# Car02.net
KiCad netlist of a schematic drawn in EAGLE
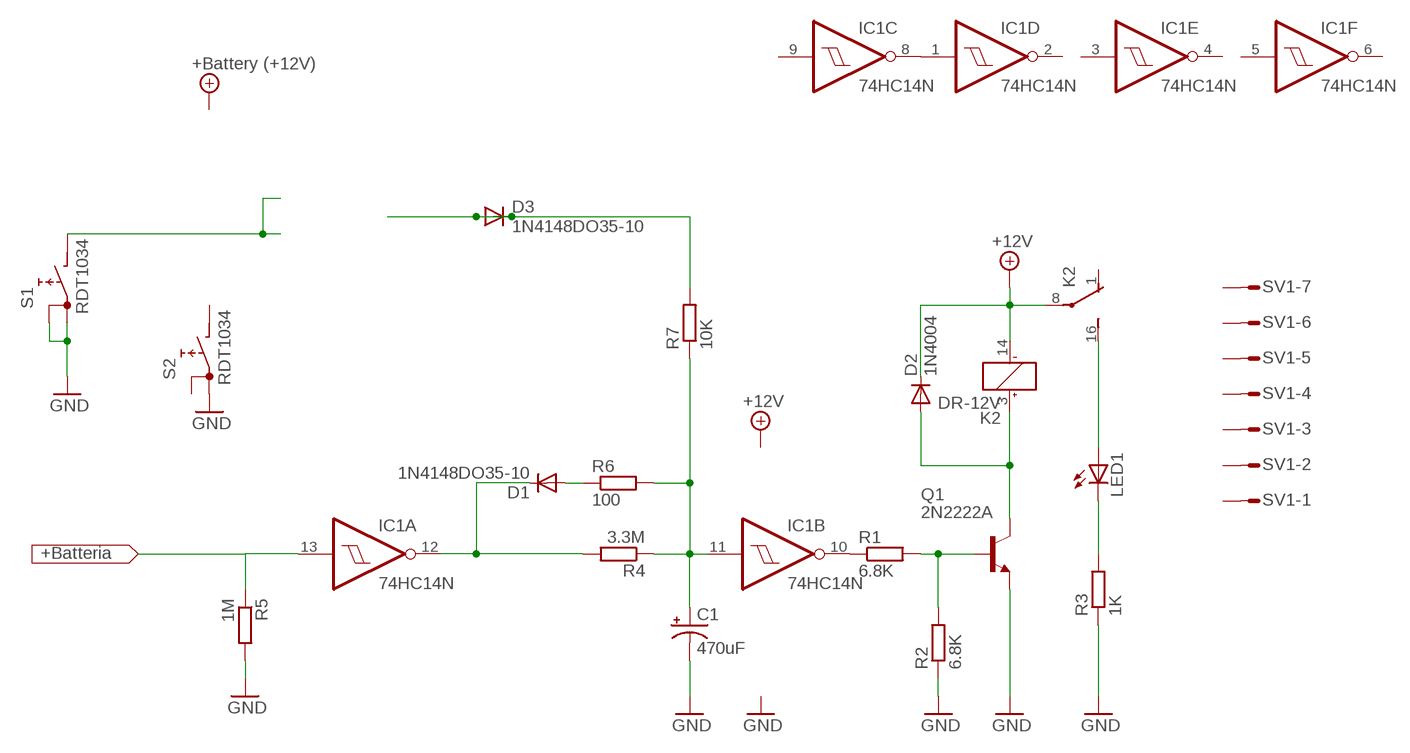
[diagram p0: schematic, sheet 1]

(export (version "E")
  (design (tool "Eeschema 10.0.6"))
  (components
    (comp (ref "C1")
      (value "470uF")
      (footprint "eagle-import:E3,5-8")
      (libsource (lib "eagle-import") (part "CPOL-USE3.5-8"))
    )
    (comp (ref "D1")
      (value "1N4148DO35-10")
      (footprint "eagle-import:DO35-10")
      (libsource (lib "eagle-import") (part "1N4148DO35-10"))
    )
    (comp (ref "D2")
      (value "1N4004")
      (footprint "eagle-import:DO41-10")
      (libsource (lib "eagle-import") (part "1N4004"))
    )
    (comp (ref "D3")
      (value "1N4148DO35-10")
      (footprint "eagle-import:DO35-10")
      (libsource (lib "eagle-import") (part "1N4148DO35-10"))
    )
    (comp (ref "IC1")
      (value "74HC14N")
      (footprint "eagle-import:DIL14")
      (libsource (lib "eagle-import") (part "7414NHC"))
    )
    (comp (ref "K2")
      (value "DR-12V")
      (footprint "eagle-import:DR-1")
      (libsource (lib "eagle-import") (part "DR-V12"))
    )
    (comp (ref "LED1")
      (value "LED")
      (footprint "eagle-import:SMARTLED-TTW")
      (libsource (lib "eagle-import") (part "LED"))
    )
    (comp (ref "Q1")
      (value "2N2222A")
      (footprint "eagle-import:TO18")
      (libsource (lib "eagle-import") (part "2N2222A"))
    )
    (comp (ref "R1")
      (value "6.8K")
      (footprint "eagle-import:0207_10")
      (libsource (lib "eagle-import") (part "R-EU_0207/10"))
    )
    (comp (ref "R2")
      (value "6.8K")
      (footprint "eagle-import:0207_10")
      (libsource (lib "eagle-import") (part "R-EU_0207/10"))
    )
    (comp (ref "R3")
      (value "1K")
      (footprint "eagle-import:0207_10")
      (libsource (lib "eagle-import") (part "R-EU_0207/10"))
    )
    (comp (ref "R4")
      (value "3.3M")
      (footprint "eagle-import:0207_10")
      (libsource (lib "eagle-import") (part "R-EU_0207/10"))
    )
    (comp (ref "R5")
      (value "1M")
      (footprint "eagle-import:0207_10")
      (libsource (lib "eagle-import") (part "R-EU_0207/10"))
    )
    (comp (ref "R6")
      (value "100")
      (footprint "eagle-import:0207_10")
      (libsource (lib "eagle-import") (part "R-EU_0207/10"))
    )
    (comp (ref "R7")
      (value "10K")
      (footprint "eagle-import:0207_10")
      (libsource (lib "eagle-import") (part "R-EU_0207/10"))
    )
    (comp (ref "S1")
      (value "RDT1034")
      (footprint "eagle-import:RDT1034")
      (libsource (lib "eagle-import") (part "RDT1034"))
    )
    (comp (ref "S2")
      (value "RDT1034")
      (footprint "eagle-import:RDT1034")
      (libsource (lib "eagle-import") (part "RDT1034"))
    )
    (comp (ref "SV1")
      (value "MT6-7")
      (footprint "eagle-import:MT6-7")
      (libsource (lib "eagle-import") (part "MT6-7"))
    )
  )
  (nets
    (net (code "1") (name "+12V") (class "Default")
      (node (ref "D2") (pin "C") (pinfunction "C_C") (pintype "passive"))
      (node (ref "K2") (pin "14") (pinfunction "-_14") (pintype "passive"))
      (node (ref "K2") (pin "8") (pinfunction "P_8") (pintype "passive"))
    )
    (net (code "3") (name "GND") (class "Default")
      (node (ref "C1") (pin "-") (pinfunction "-_-") (pintype "passive"))
      (node (ref "Q1") (pin "1") (pinfunction "E_1") (pintype "passive"))
      (node (ref "R2") (pin "1") (pinfunction "1_1") (pintype "passive"))
      (node (ref "R3") (pin "1") (pinfunction "1_1") (pintype "passive"))
      (node (ref "R5") (pin "2") (pinfunction "2_2") (pintype "passive"))
      (node (ref "S1") (pin "A") (pinfunction "A_A") (pintype "passive"))
      (node (ref "S1") (pin "A1") (pinfunction "A1_A1") (pintype "passive"))
      (node (ref "S2") (pin "A1") (pinfunction "A1_A1") (pintype "passive"))
    )
    (net (code "4") (name "Net-(D1-PadA)") (class "Default")
      (node (ref "D1") (pin "A") (pinfunction "A_A") (pintype "passive"))
      (node (ref "R6") (pin "1") (pinfunction "1_1") (pintype "passive"))
    )
    (net (code "5") (name "Net-(D3-PadA)") (class "Default")
      (node (ref "D3") (pin "A") (pinfunction "A_A") (pintype "passive"))
      (node (ref "D3") (pin "C") (pinfunction "C_C") (pintype "passive"))
      (node (ref "R7") (pin "2") (pinfunction "2_2") (pintype "passive"))
    )
    (net (code "6") (name "Net-(IC1A-I)") (class "Default")
      (node (ref "IC1") (pin "13") (pinfunction "I_13") (pintype "input"))
      (node (ref "R5") (pin "1") (pinfunction "1_1") (pintype "passive"))
    )
    (net (code "7") (name "Net-(IC1A-O)") (class "Default")
      (node (ref "D1") (pin "C") (pinfunction "C_C") (pintype "passive"))
      (node (ref "IC1") (pin "12") (pinfunction "O_12") (pintype "output"))
      (node (ref "R4") (pin "2") (pinfunction "2_2") (pintype "passive"))
    )
    (net (code "8") (name "Net-(IC1B-I)") (class "Default")
      (node (ref "C1") (pin "+") (pinfunction "+_+") (pintype "passive"))
      (node (ref "IC1") (pin "11") (pinfunction "I_11") (pintype "input"))
      (node (ref "R4") (pin "1") (pinfunction "1_1") (pintype "passive"))
      (node (ref "R6") (pin "2") (pinfunction "2_2") (pintype "passive"))
      (node (ref "R7") (pin "1") (pinfunction "1_1") (pintype "passive"))
    )
    (net (code "9") (name "Net-(IC1B-O)") (class "Default")
      (node (ref "IC1") (pin "10") (pinfunction "O_10") (pintype "output"))
      (node (ref "R1") (pin "1") (pinfunction "1_1") (pintype "passive"))
    )
    (net (code "10") (name "Net-(IC1C-O)") (class "Default")
      (node (ref "IC1") (pin "1") (pinfunction "I_1") (pintype "input"))
      (node (ref "IC1") (pin "8") (pinfunction "O_8") (pintype "output"))
    )
    (net (code "11") (name "Net-(K2A-+)") (class "Default")
      (node (ref "D2") (pin "A") (pinfunction "A_A") (pintype "passive"))
      (node (ref "K2") (pin "3") (pinfunction "+_3") (pintype "passive"))
      (node (ref "Q1") (pin "3") (pinfunction "C_3") (pintype "passive"))
    )
    (net (code "12") (name "Net-(K2B-S)") (class "Default")
      (node (ref "K2") (pin "16") (pinfunction "S_16") (pintype "passive"))
      (node (ref "LED1") (pin "A@1") (pinfunction "A_A@1") (pintype "passive"))
    )
    (net (code "13") (name "Net-(LED1-C)") (class "Default")
      (node (ref "LED1") (pin "C@1") (pinfunction "C_C@1") (pintype "passive"))
      (node (ref "R3") (pin "2") (pinfunction "2_2") (pintype "passive"))
    )
    (net (code "14") (name "Net-(Q1-B)") (class "Default")
      (node (ref "Q1") (pin "2") (pinfunction "B_2") (pintype "passive"))
      (node (ref "R1") (pin "2") (pinfunction "2_2") (pintype "passive"))
      (node (ref "R2") (pin "2") (pinfunction "2_2") (pintype "passive"))
    )
    (net (code "15") (name "unconnected-(IC1C-I-Pad9)") (class "Default")
      (node (ref "IC1") (pin "9") (pinfunction "I_9") (pintype "input"))
    )
    (net (code "16") (name "unconnected-(IC1D-O-Pad2)") (class "Default")
      (node (ref "IC1") (pin "2") (pinfunction "O_2") (pintype "output"))
    )
    (net (code "17") (name "unconnected-(IC1E-I-Pad3)") (class "Default")
      (node (ref "IC1") (pin "3") (pinfunction "I_3") (pintype "input"))
    )
    (net (code "18") (name "unconnected-(IC1E-O-Pad4)") (class "Default")
      (node (ref "IC1") (pin "4") (pinfunction "O_4") (pintype "output"))
    )
    (net (code "19") (name "unconnected-(IC1F-I-Pad5)") (class "Default")
      (node (ref "IC1") (pin "5") (pinfunction "I_5") (pintype "input"))
    )
    (net (code "20") (name "unconnected-(IC1F-O-Pad6)") (class "Default")
      (node (ref "IC1") (pin "6") (pinfunction "O_6") (pintype "output"))
    )
    (net (code "21") (name "unconnected-(K2B-O-Pad1)") (class "Default")
      (node (ref "K2") (pin "1") (pinfunction "O_1") (pintype "passive"))
    )
    (net (code "22") (name "unconnected-(S1-PadB)") (class "Default")
      (node (ref "S1") (pin "B") (pinfunction "B_B") (pintype "passive"))
    )
    (net (code "23") (name "unconnected-(S2-PadA)") (class "Default")
      (node (ref "S2") (pin "A") (pinfunction "A_A") (pintype "passive"))
    )
    (net (code "24") (name "unconnected-(S2-PadB)") (class "Default")
      (node (ref "S2") (pin "B") (pinfunction "B_B") (pintype "passive"))
    )
    (net (code "25") (name "unconnected-(SV1A-S-Pad1)") (class "Default")
      (node (ref "SV1") (pin "1") (pinfunction "S_1") (pintype "passive"))
    )
    (net (code "26") (name "unconnected-(SV1B-S-Pad2)") (class "Default")
      (node (ref "SV1") (pin "2") (pinfunction "S_2") (pintype "passive"))
    )
    (net (code "27") (name "unconnected-(SV1C-S-Pad3)") (class "Default")
      (node (ref "SV1") (pin "3") (pinfunction "S_3") (pintype "passive"))
    )
    (net (code "28") (name "unconnected-(SV1D-S-Pad4)") (class "Default")
      (node (ref "SV1") (pin "4") (pinfunction "S_4") (pintype "passive"))
    )
    (net (code "29") (name "unconnected-(SV1E-S-Pad5)") (class "Default")
      (node (ref "SV1") (pin "5") (pinfunction "S_5") (pintype "passive"))
    )
    (net (code "30") (name "unconnected-(SV1F-S-Pad6)") (class "Default")
      (node (ref "SV1") (pin "6") (pinfunction "S_6") (pintype "passive"))
    )
    (net (code "31") (name "unconnected-(SV1G-S-Pad7)") (class "Default")
      (node (ref "SV1") (pin "7") (pinfunction "S_7") (pintype "passive"))
    )
  )
)
